# puenteH.net
KiCad netlist of a schematic drawn in EAGLE
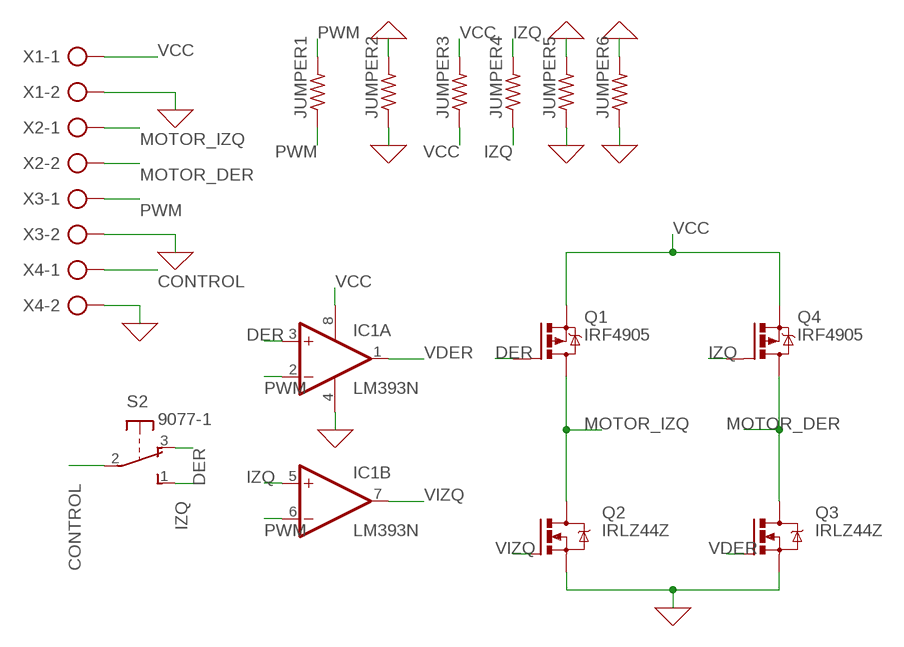
[diagram p0: schematic, sheet 1]

(export (version "E")
  (design (tool "Eeschema 10.0.6"))
  (components
    (comp (ref "IC1")
      (value "LM393N")
      (footprint "eagle-import:DIL08")
      (libsource (lib "eagle-import") (part "LM393N"))
    )
    (comp (ref "JUMPER1")
      (value "R-US_0204/5")
      (footprint "eagle-import:0204_5")
      (libsource (lib "eagle-import") (part "R-US_0204/5"))
    )
    (comp (ref "JUMPER2")
      (value "R-US_0204/7")
      (footprint "eagle-import:0204_7")
      (libsource (lib "eagle-import") (part "R-US_0204/7"))
    )
    (comp (ref "JUMPER3")
      (value "R-US_0204/5")
      (footprint "eagle-import:0204_5")
      (libsource (lib "eagle-import") (part "R-US_0204/5"))
    )
    (comp (ref "JUMPER4")
      (value "R-US_0204/7")
      (footprint "eagle-import:0204_7")
      (libsource (lib "eagle-import") (part "R-US_0204/7"))
    )
    (comp (ref "JUMPER5")
      (value "R-US_0204/5")
      (footprint "eagle-import:0204_5")
      (libsource (lib "eagle-import") (part "R-US_0204/5"))
    )
    (comp (ref "JUMPER6")
      (value "R-US_0204/7")
      (footprint "eagle-import:0204_7")
      (libsource (lib "eagle-import") (part "R-US_0204/7"))
    )
    (comp (ref "Q1")
      (value "IRF4905")
      (footprint "eagle-import:TO220BH")
      (libsource (lib "eagle-import") (part "IRF4905"))
    )
    (comp (ref "Q2")
      (value "IRLZ44Z")
      (footprint "eagle-import:TO220BH")
      (libsource (lib "eagle-import") (part "IRLZ44Z"))
    )
    (comp (ref "Q3")
      (value "IRLZ44Z")
      (footprint "eagle-import:TO220BH")
      (libsource (lib "eagle-import") (part "IRLZ44Z"))
    )
    (comp (ref "Q4")
      (value "IRF4905")
      (footprint "eagle-import:TO220BH")
      (libsource (lib "eagle-import") (part "IRF4905"))
    )
    (comp (ref "S2")
      (value "9077-1")
      (footprint "eagle-import:9077-1")
      (libsource (lib "eagle-import") (part "9077-1"))
    )
    (comp (ref "X1")
      (value "AK300/2")
      (footprint "eagle-import:AK300_2")
      (libsource (lib "eagle-import") (part "AK300/2"))
    )
    (comp (ref "X2")
      (value "AK300/2")
      (footprint "eagle-import:AK300_2")
      (libsource (lib "eagle-import") (part "AK300/2"))
    )
    (comp (ref "X3")
      (value "AK300/2")
      (footprint "eagle-import:AK300_2")
      (libsource (lib "eagle-import") (part "AK300/2"))
    )
    (comp (ref "X4")
      (value "AK300/2")
      (footprint "eagle-import:AK300_2")
      (libsource (lib "eagle-import") (part "AK300/2"))
    )
  )
  (nets
    (net (code "1") (name "/CONTROL") (class "Default")
      (node (ref "S2") (pin "2") (pinfunction "P_2") (pintype "passive"))
      (node (ref "X4") (pin "1") (pinfunction "KL_1") (pintype "passive"))
    )
    (net (code "2") (name "/DER") (class "Default")
      (node (ref "IC1") (pin "3") (pinfunction "+IN_3") (pintype "input"))
      (node (ref "Q1") (pin "G") (pinfunction "G_G") (pintype "passive"))
      (node (ref "S2") (pin "3") (pinfunction "O_3") (pintype "passive"))
    )
    (net (code "3") (name "/IZQ") (class "Default")
      (node (ref "IC1") (pin "5") (pinfunction "+IN_5") (pintype "input"))
      (node (ref "JUMPER4") (pin "1") (pinfunction "1_1") (pintype "passive"))
      (node (ref "JUMPER4") (pin "2") (pinfunction "2_2") (pintype "passive"))
      (node (ref "Q4") (pin "G") (pinfunction "G_G") (pintype "passive"))
      (node (ref "S2") (pin "1") (pinfunction "S_1") (pintype "passive"))
    )
    (net (code "4") (name "/MOTOR_DER") (class "Default")
      (node (ref "Q3") (pin "D") (pinfunction "D_D") (pintype "passive"))
      (node (ref "Q4") (pin "D") (pinfunction "D_D") (pintype "passive"))
      (node (ref "X2") (pin "2") (pinfunction "KL_2") (pintype "passive"))
    )
    (net (code "5") (name "/MOTOR_IZQ") (class "Default")
      (node (ref "Q1") (pin "D") (pinfunction "D_D") (pintype "passive"))
      (node (ref "Q2") (pin "D") (pinfunction "D_D") (pintype "passive"))
      (node (ref "X2") (pin "1") (pinfunction "KL_1") (pintype "passive"))
    )
    (net (code "6") (name "/PWM") (class "Default")
      (node (ref "IC1") (pin "2") (pinfunction "-IN_2") (pintype "input"))
      (node (ref "IC1") (pin "6") (pinfunction "-IN_6") (pintype "input"))
      (node (ref "JUMPER1") (pin "1") (pinfunction "1_1") (pintype "passive"))
      (node (ref "JUMPER1") (pin "2") (pinfunction "2_2") (pintype "passive"))
      (node (ref "X3") (pin "1") (pinfunction "KL_1") (pintype "passive"))
    )
    (net (code "7") (name "/VCC") (class "Default")
      (node (ref "IC1") (pin "8") (pinfunction "V+_8") (pintype "power_in"))
      (node (ref "JUMPER3") (pin "1") (pinfunction "1_1") (pintype "passive"))
      (node (ref "JUMPER3") (pin "2") (pinfunction "2_2") (pintype "passive"))
      (node (ref "Q1") (pin "S") (pinfunction "S_S") (pintype "passive"))
      (node (ref "Q4") (pin "S") (pinfunction "S_S") (pintype "passive"))
      (node (ref "X1") (pin "1") (pinfunction "KL_1") (pintype "passive"))
    )
    (net (code "8") (name "/VDER") (class "Default")
      (node (ref "IC1") (pin "1") (pinfunction "OUT_1") (pintype "output"))
      (node (ref "Q3") (pin "G") (pinfunction "G_G") (pintype "passive"))
    )
    (net (code "9") (name "/VIZQ") (class "Default")
      (node (ref "IC1") (pin "7") (pinfunction "OUT_7") (pintype "output"))
      (node (ref "Q2") (pin "G") (pinfunction "G_G") (pintype "passive"))
    )
    (net (code "10") (name "GND") (class "Default")
      (node (ref "IC1") (pin "4") (pinfunction "V-_4") (pintype "power_in"))
      (node (ref "JUMPER2") (pin "1") (pinfunction "1_1") (pintype "passive"))
      (node (ref "JUMPER2") (pin "2") (pinfunction "2_2") (pintype "passive"))
      (node (ref "JUMPER5") (pin "1") (pinfunction "1_1") (pintype "passive"))
      (node (ref "JUMPER5") (pin "2") (pinfunction "2_2") (pintype "passive"))
      (node (ref "JUMPER6") (pin "1") (pinfunction "1_1") (pintype "passive"))
      (node (ref "JUMPER6") (pin "2") (pinfunction "2_2") (pintype "passive"))
      (node (ref "Q2") (pin "S") (pinfunction "S_S") (pintype "passive"))
      (node (ref "Q3") (pin "S") (pinfunction "S_S") (pintype "passive"))
      (node (ref "X1") (pin "2") (pinfunction "KL_2") (pintype "passive"))
      (node (ref "X3") (pin "2") (pinfunction "KL_2") (pintype "passive"))
      (node (ref "X4") (pin "2") (pinfunction "KL_2") (pintype "passive"))
    )
  )
)
